# APRDL_2016_4L.net
KiCad netlist of a schematic drawn in EAGLE
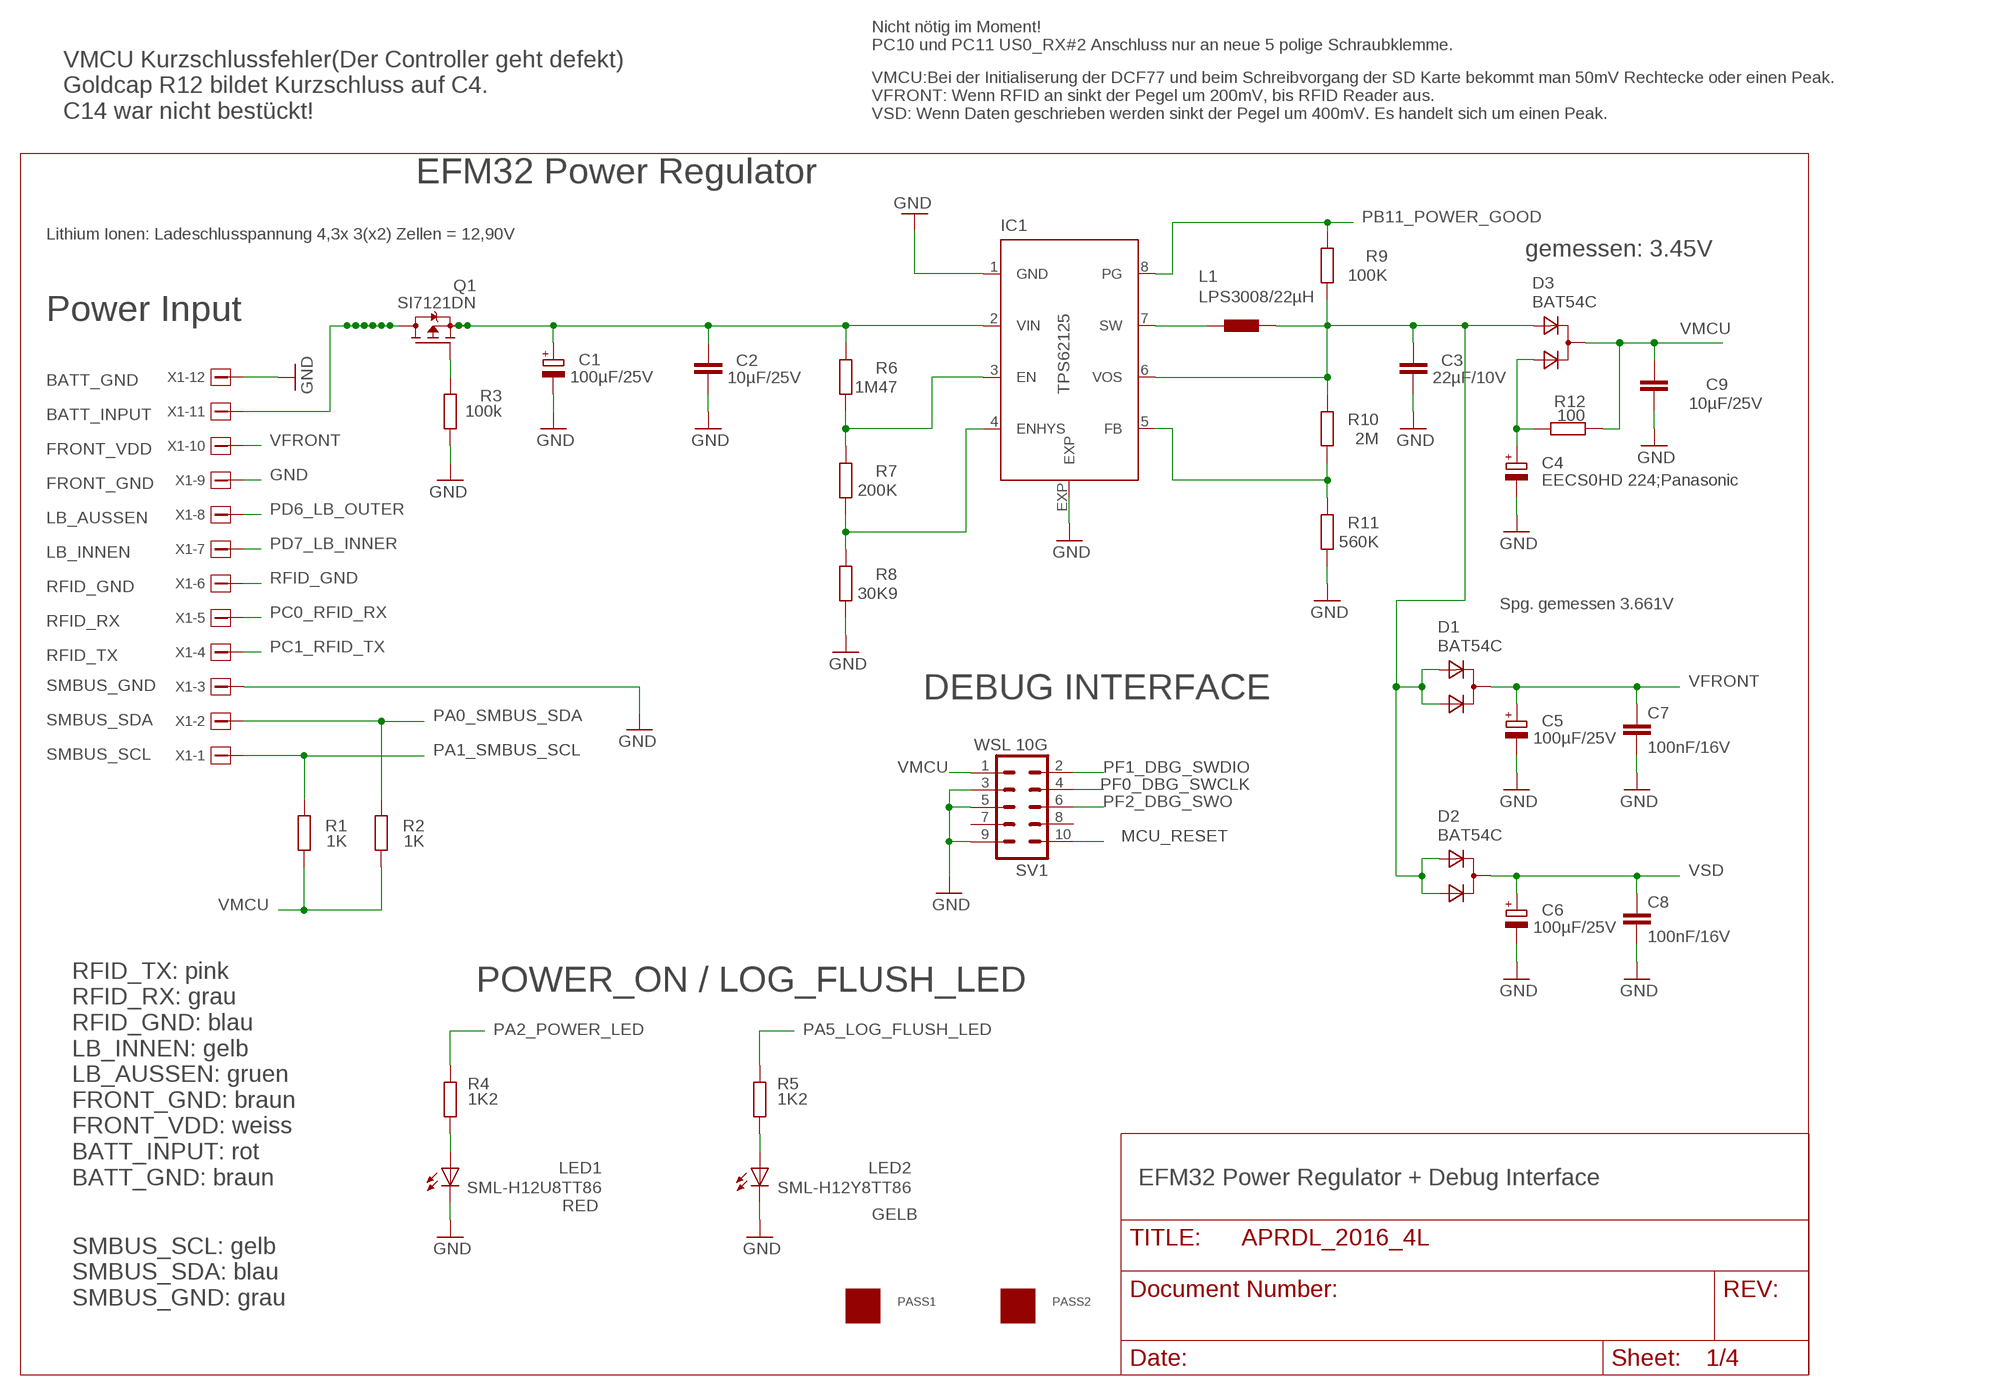
[diagram p0: schematic, sheet 1]
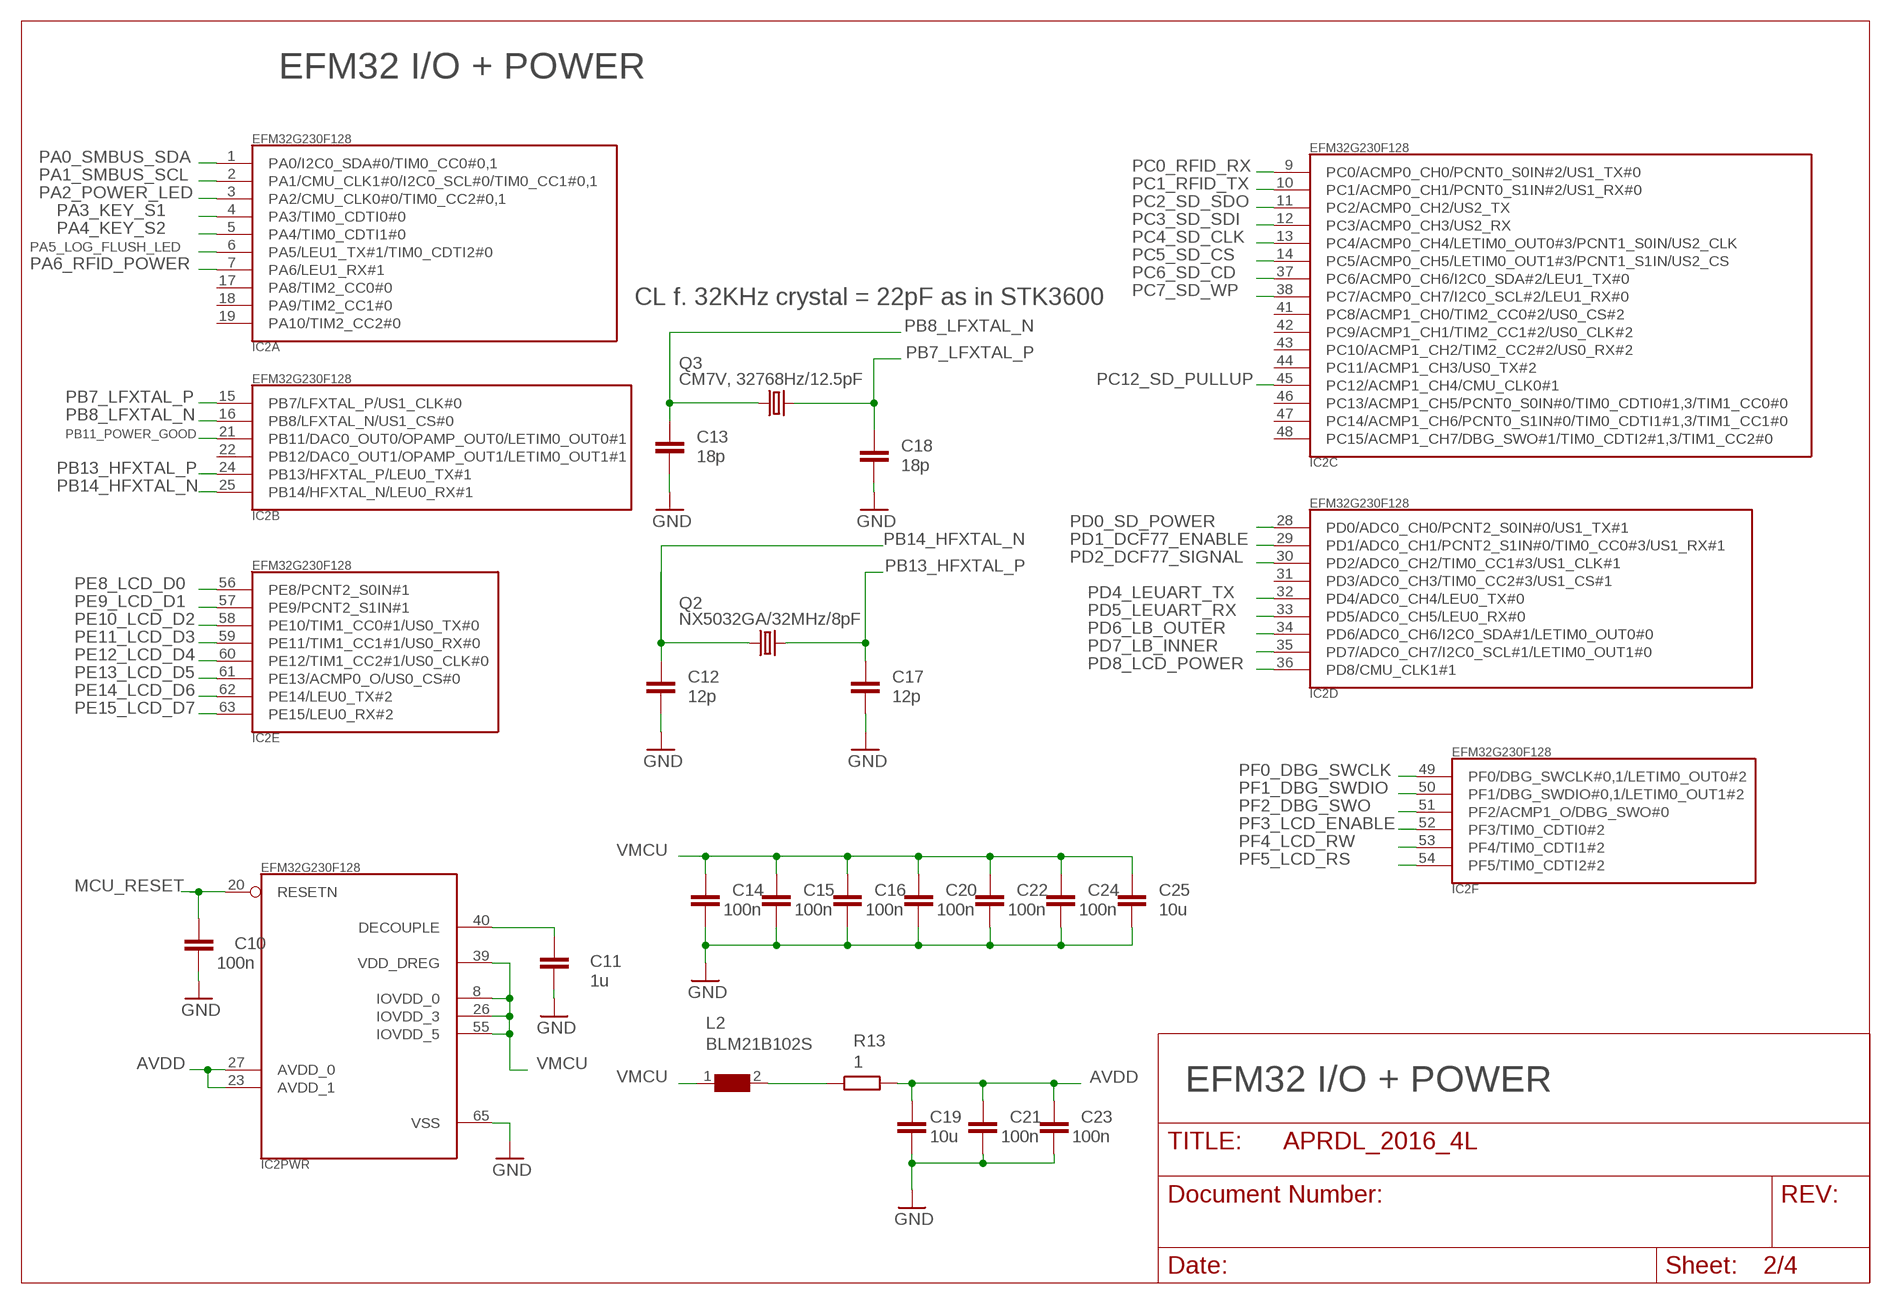
[diagram p1: schematic, sheet 2]
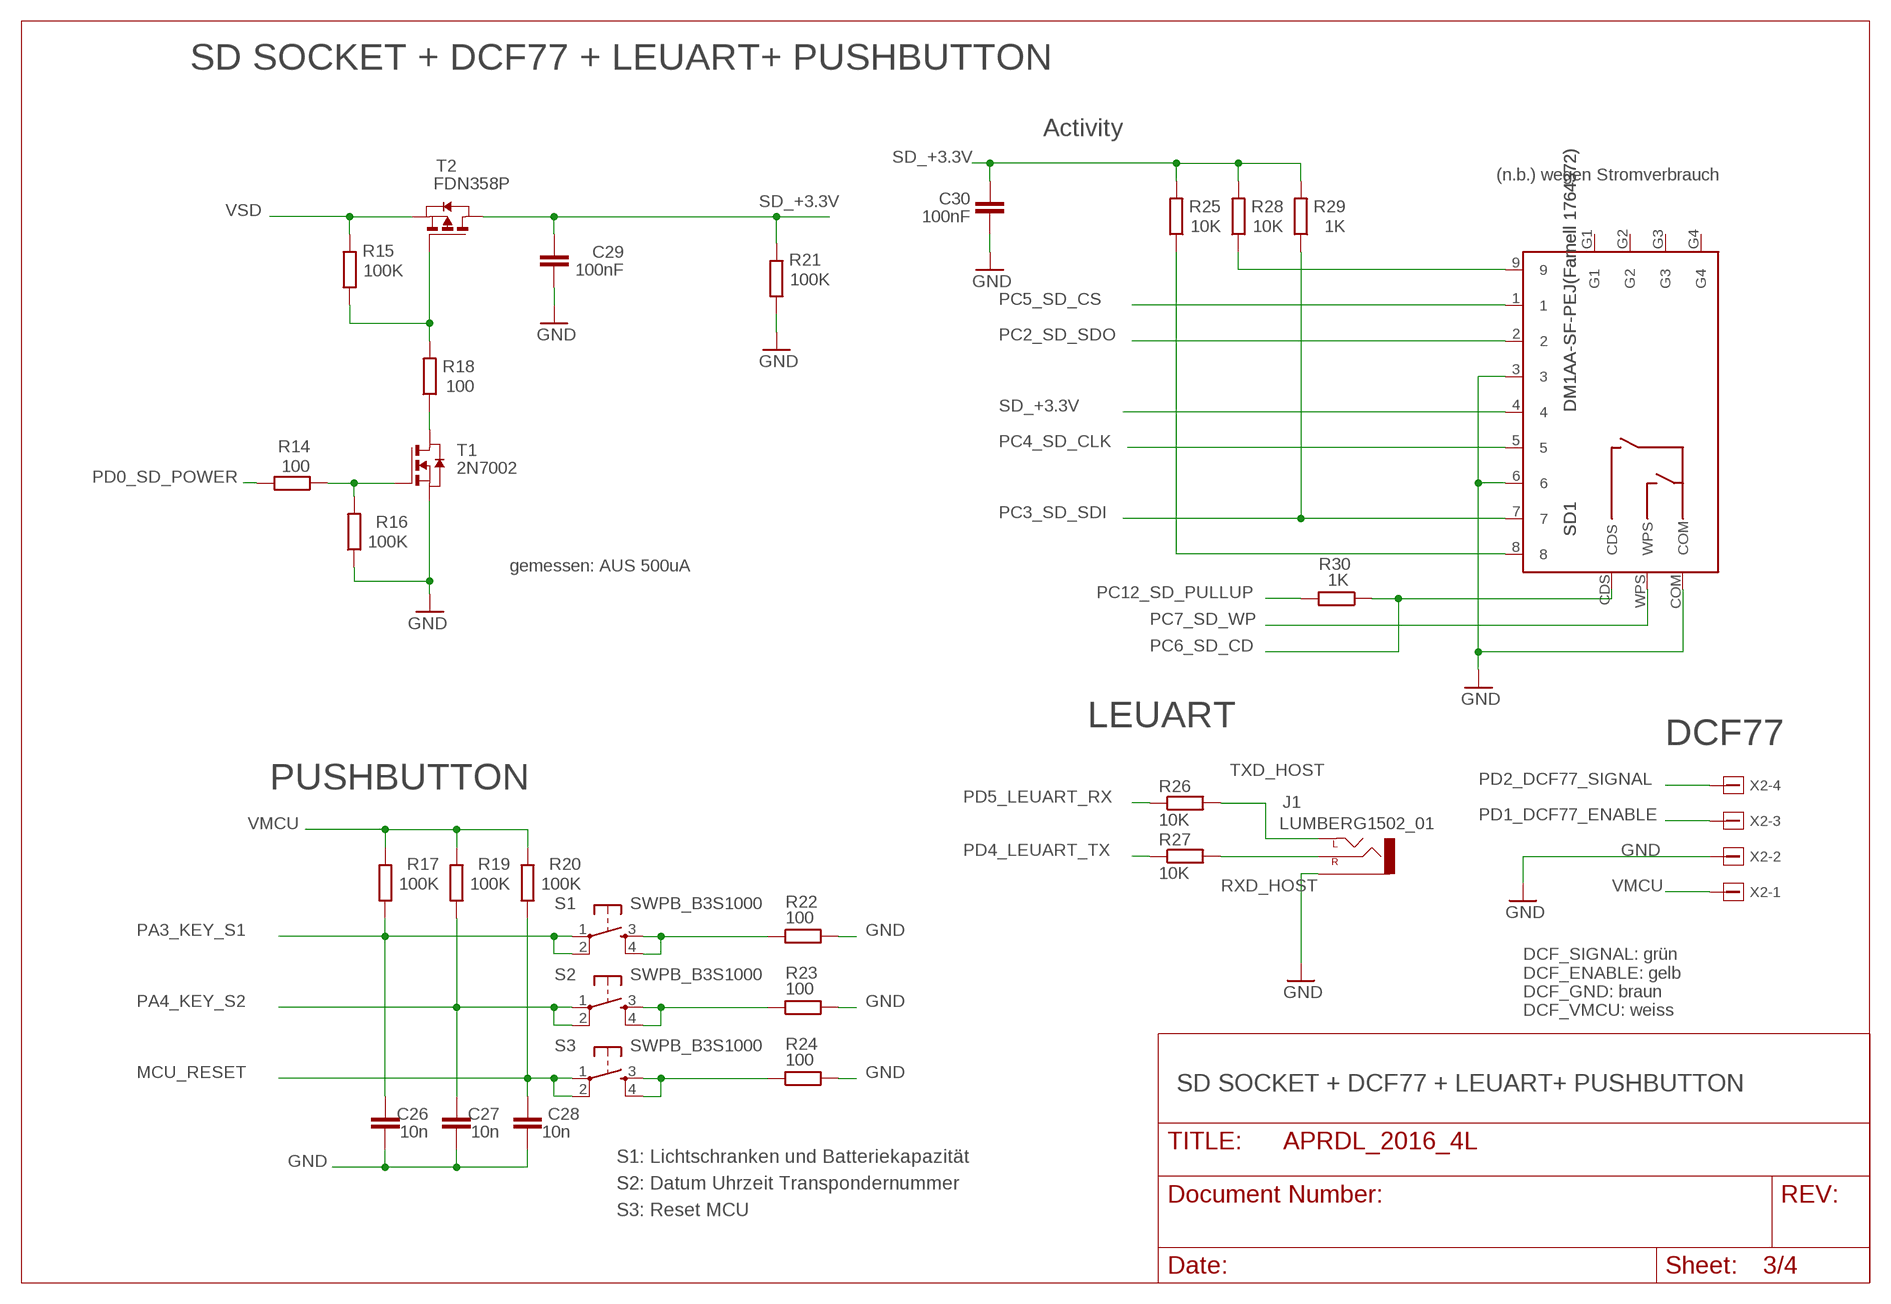
[diagram p2: schematic, sheet 3]
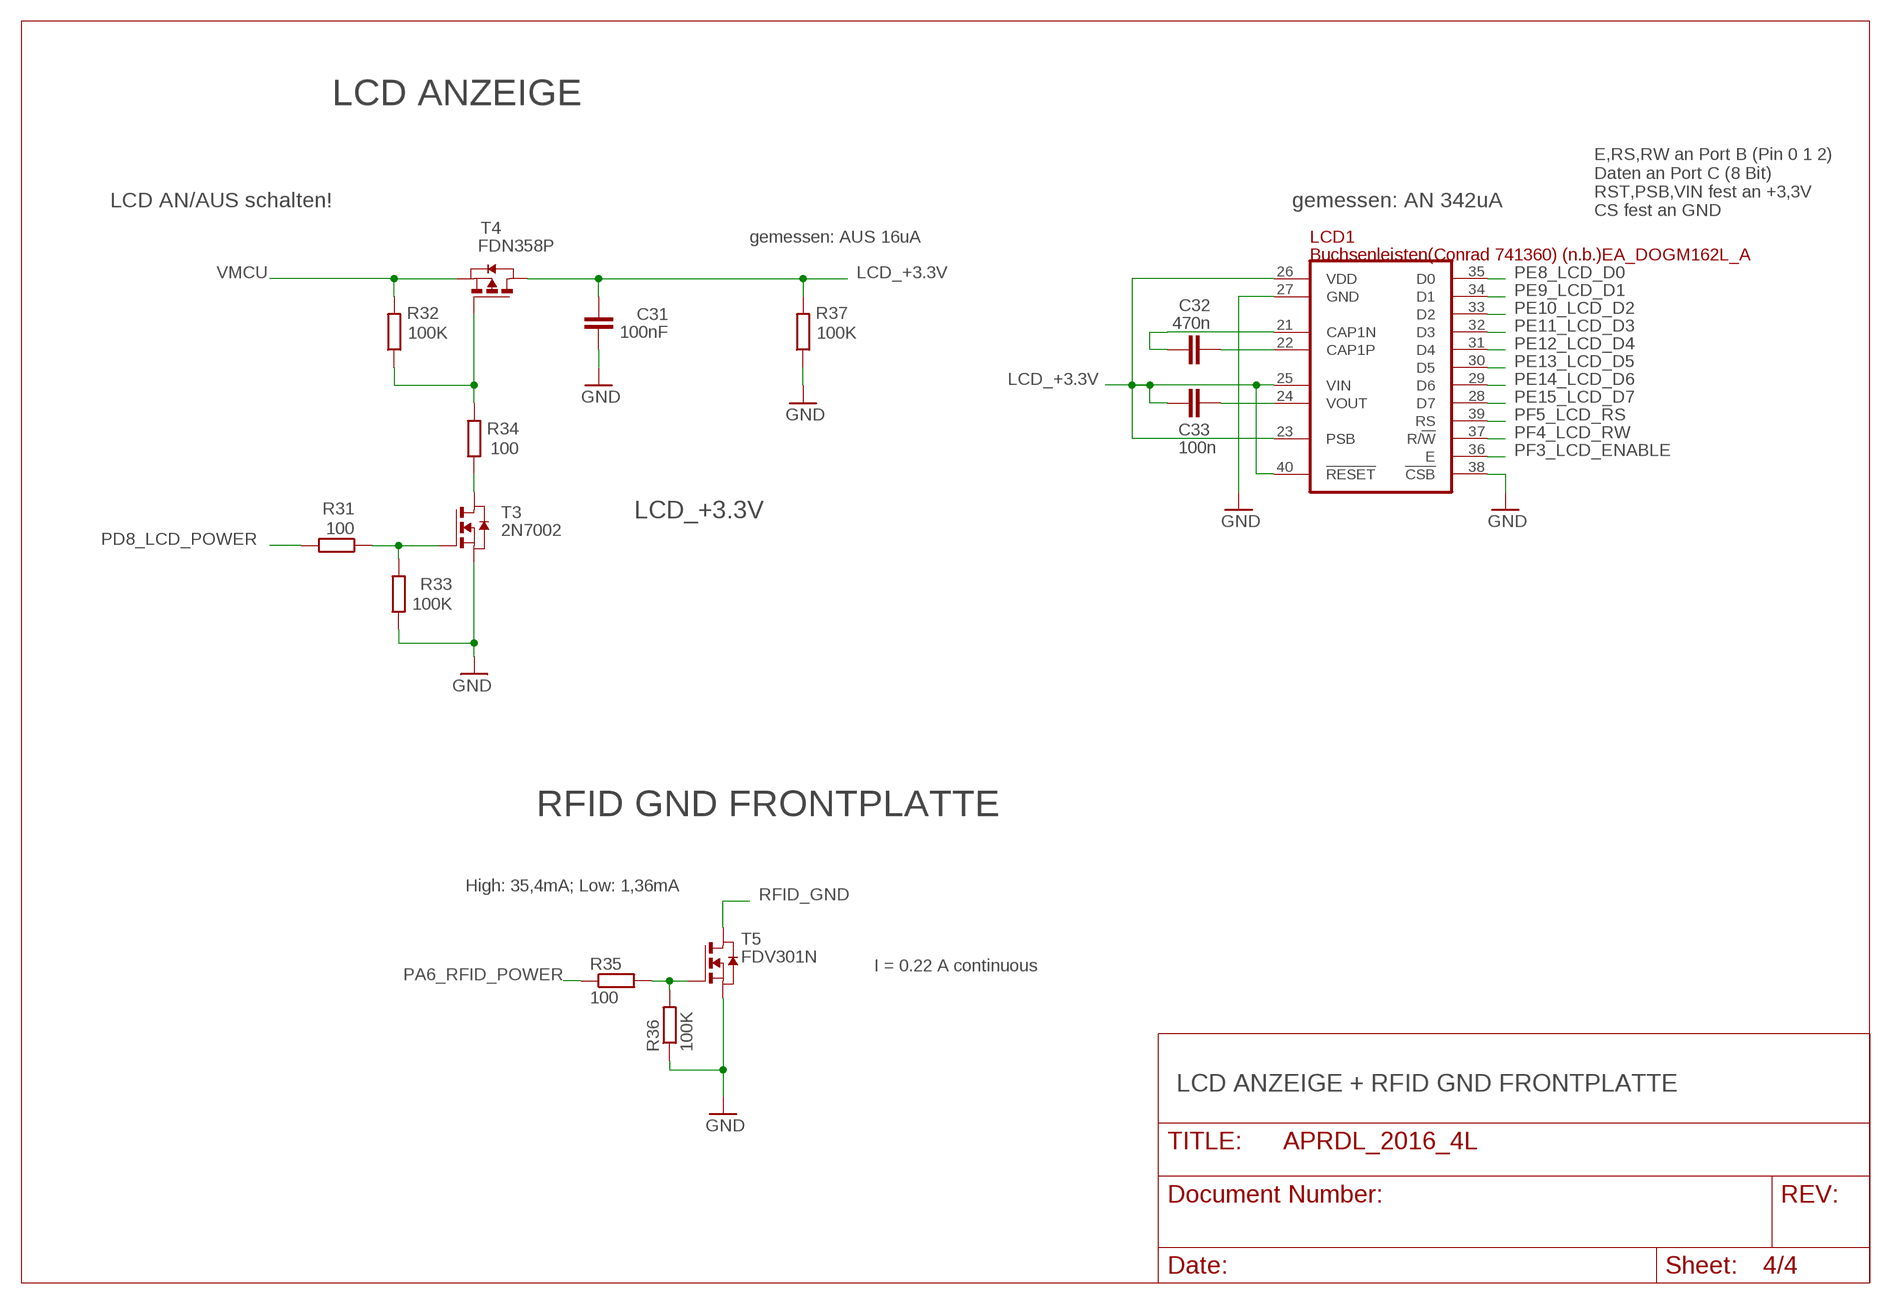
[diagram p3: schematic, sheet 4]

(export (version "E")
  (design (tool "Eeschema 10.0.6"))
  (components
    (comp (ref "C10")
      (value "100n")
      (footprint "eagle-import:C0805")
      (libsource (lib "eagle-import") (part "C-EUC0805"))
    )
    (comp (ref "C11")
      (value "1u")
      (footprint "eagle-import:C0805")
      (libsource (lib "eagle-import") (part "C-EUC0805"))
    )
    (comp (ref "C12")
      (value "12p")
      (footprint "eagle-import:C0805")
      (libsource (lib "eagle-import") (part "C-EUC0805"))
    )
    (comp (ref "C13")
      (value "18p")
      (footprint "eagle-import:C0805")
      (libsource (lib "eagle-import") (part "C-EUC0805"))
    )
    (comp (ref "C14")
      (value "100n")
      (footprint "eagle-import:C0805")
      (libsource (lib "eagle-import") (part "C-EUC0805"))
    )
    (comp (ref "C15")
      (value "100n")
      (footprint "eagle-import:C0805")
      (libsource (lib "eagle-import") (part "C-EUC0805"))
    )
    (comp (ref "C16")
      (value "100n")
      (footprint "eagle-import:C0805")
      (libsource (lib "eagle-import") (part "C-EUC0805"))
    )
    (comp (ref "C17")
      (value "12p")
      (footprint "eagle-import:C0805")
      (libsource (lib "eagle-import") (part "C-EUC0805"))
    )
    (comp (ref "C18")
      (value "18p")
      (footprint "eagle-import:C0805")
      (libsource (lib "eagle-import") (part "C-EUC0805"))
    )
    (comp (ref "C19")
      (value "10u")
      (footprint "eagle-import:C0805")
      (libsource (lib "eagle-import") (part "C-EUC0805"))
    )
    (comp (ref "C20")
      (value "100n")
      (footprint "eagle-import:C0805")
      (libsource (lib "eagle-import") (part "C-EUC0805"))
    )
    (comp (ref "C21")
      (value "100n")
      (footprint "eagle-import:C0805")
      (libsource (lib "eagle-import") (part "C-EUC0805"))
    )
    (comp (ref "C22")
      (value "100n")
      (footprint "eagle-import:C0805")
      (libsource (lib "eagle-import") (part "C-EUC0805"))
    )
    (comp (ref "C23")
      (value "100n")
      (footprint "eagle-import:C0805")
      (libsource (lib "eagle-import") (part "C-EUC0805"))
    )
    (comp (ref "C24")
      (value "100n")
      (footprint "eagle-import:C0805")
      (libsource (lib "eagle-import") (part "C-EUC0805"))
    )
    (comp (ref "C25")
      (value "10u")
      (footprint "eagle-import:C0805")
      (libsource (lib "eagle-import") (part "C-EUC0805"))
    )
    (comp (ref "IC2")
      (value "EFM32G230F128")
      (footprint "eagle-import:QFN64")
      (libsource (lib "eagle-import") (part "EFM32G230F128"))
    )
    (comp (ref "L2")
      (value "BLM21B102S")
      (footprint "eagle-import:0805")
      (fields (field (name "MPN") "7427920"))
      (libsource (lib "eagle-import") (part "WE-CBF_0805-7427920"))
    )
    (comp (ref "Q2")
      (value "NX5032GA/32MHz/8pF")
      (footprint "eagle-import:CRYSTAL2P5.0X3.2")
      (libsource (lib "eagle-import") (part "CRYSTAL2P5.0X3.2"))
    )
    (comp (ref "Q3")
      (value "CM7V, 32768Hz/12.5pF")
      (footprint "eagle-import:CRYSTAL2P3.2X1.5")
      (libsource (lib "eagle-import") (part "CRYSTAL2P"))
    )
    (comp (ref "R13")
      (value "1")
      (footprint "eagle-import:R0805")
      (libsource (lib "eagle-import") (part "R-EU_R0805"))
    )
    (comp (ref "C31")
      (value "100nF")
      (footprint "eagle-import:C0603")
      (libsource (lib "eagle-import") (part "resistor_C-EUC0603"))
    )
    (comp (ref "C32")
      (value "470n")
      (footprint "eagle-import:C0805")
      (libsource (lib "eagle-import") (part "C-EUC0805"))
    )
    (comp (ref "C33")
      (value "100n")
      (footprint "eagle-import:C1206")
      (libsource (lib "eagle-import") (part "C-EUC1206"))
    )
    (comp (ref "LCD1")
      (value "Buchsenleisten(Conrad 741360) (n.b.)EA_DOGM162L_A")
      (footprint "eagle-import:EA_DOGM")
      (libsource (lib "eagle-import") (part "EA_DOGM162"))
    )
    (comp (ref "R31")
      (value "100")
      (footprint "eagle-import:R0805")
      (libsource (lib "eagle-import") (part "resistor_R-EU_R0805"))
    )
    (comp (ref "R32")
      (value "100K")
      (footprint "eagle-import:R0805")
      (libsource (lib "eagle-import") (part "resistor_R-EU_R0805"))
    )
    (comp (ref "R33")
      (value "100K")
      (footprint "eagle-import:R0805")
      (libsource (lib "eagle-import") (part "resistor_R-EU_R0805"))
    )
    (comp (ref "R34")
      (value "100")
      (footprint "eagle-import:R0805")
      (libsource (lib "eagle-import") (part "resistor_R-EU_R0805"))
    )
    (comp (ref "R35")
      (value "100")
      (footprint "eagle-import:R0805")
      (libsource (lib "eagle-import") (part "R-EU_R0805"))
    )
    (comp (ref "R36")
      (value "100K")
      (footprint "eagle-import:R0805")
      (libsource (lib "eagle-import") (part "R-EU_R0805"))
    )
    (comp (ref "R37")
      (value "100K")
      (footprint "eagle-import:R0805")
      (libsource (lib "eagle-import") (part "resistor_R-EU_R0805"))
    )
    (comp (ref "T3")
      (value "2N7002")
      (footprint "eagle-import:ZETEX_SOT-23")
      (libsource (lib "eagle-import") (part "ZETEX_NMOSSOT23"))
    )
    (comp (ref "T4")
      (value "FDN358P")
      (footprint "eagle-import:ZETEX_SOT-23")
      (libsource (lib "eagle-import") (part "ZETEX_PMOSSOT23"))
    )
    (comp (ref "T5")
      (value "FDV301N")
      (footprint "eagle-import:SOT-23")
      (fields (field (name "OC_FARNELL") "unknown") (field (name "OC_NEWARK") "unknown"))
      (libsource (lib "eagle-import") (part "NMOSSOT23"))
    )
    (comp (ref "C26")
      (value "10n")
      (footprint "eagle-import:C0603")
      (libsource (lib "eagle-import") (part "resistor_C-EUC0603"))
    )
    (comp (ref "C27")
      (value "10n")
      (footprint "eagle-import:C0603")
      (libsource (lib "eagle-import") (part "resistor_C-EUC0603"))
    )
    (comp (ref "C28")
      (value "10n")
      (footprint "eagle-import:C0603")
      (libsource (lib "eagle-import") (part "resistor_C-EUC0603"))
    )
    (comp (ref "C29")
      (value "100nF")
      (footprint "eagle-import:C0603")
      (libsource (lib "eagle-import") (part "resistor_C-EUC0603"))
    )
    (comp (ref "C30")
      (value "100nF")
      (footprint "eagle-import:C0603")
      (libsource (lib "eagle-import") (part "resistor_C-EUC0603"))
    )
    (comp (ref "J1")
      (value "LUMBERG1502_01")
      (footprint "eagle-import:LUMBERG1502_01")
      (libsource (lib "eagle-import") (part "LUMBERG1502_01"))
    )
    (comp (ref "R14")
      (value "100")
      (footprint "eagle-import:R0805")
      (libsource (lib "eagle-import") (part "resistor_R-EU_R0805"))
    )
    (comp (ref "R15")
      (value "100K")
      (footprint "eagle-import:R0805")
      (libsource (lib "eagle-import") (part "resistor_R-EU_R0805"))
    )
    (comp (ref "R16")
      (value "100K")
      (footprint "eagle-import:R0805")
      (libsource (lib "eagle-import") (part "resistor_R-EU_R0805"))
    )
    (comp (ref "R17")
      (value "100K")
      (footprint "eagle-import:R0805")
      (libsource (lib "eagle-import") (part "resistor_R-EU_R0805"))
    )
    (comp (ref "R18")
      (value "100")
      (footprint "eagle-import:R0805")
      (libsource (lib "eagle-import") (part "resistor_R-EU_R0805"))
    )
    (comp (ref "R19")
      (value "100K")
      (footprint "eagle-import:R0805")
      (libsource (lib "eagle-import") (part "resistor_R-EU_R0805"))
    )
    (comp (ref "R20")
      (value "100K")
      (footprint "eagle-import:R0805")
      (libsource (lib "eagle-import") (part "resistor_R-EU_R0805"))
    )
    (comp (ref "R21")
      (value "100K")
      (footprint "eagle-import:R0805")
      (libsource (lib "eagle-import") (part "resistor_R-EU_R0805"))
    )
    (comp (ref "R22")
      (value "100")
      (footprint "eagle-import:R0805")
      (libsource (lib "eagle-import") (part "resistor_R-EU_R0805"))
    )
    (comp (ref "R23")
      (value "100")
      (footprint "eagle-import:R0805")
      (libsource (lib "eagle-import") (part "resistor_R-EU_R0805"))
    )
    (comp (ref "R24")
      (value "100")
      (footprint "eagle-import:R0805")
      (libsource (lib "eagle-import") (part "resistor_R-EU_R0805"))
    )
    (comp (ref "R25")
      (value "10K")
      (footprint "eagle-import:R0805")
      (libsource (lib "eagle-import") (part "resistor_R-EU_R0805"))
    )
    (comp (ref "R26")
      (value "10K")
      (footprint "eagle-import:R0805")
      (libsource (lib "eagle-import") (part "R-EU_R0805"))
    )
    (comp (ref "R27")
      (value "10K")
      (footprint "eagle-import:R0805")
      (libsource (lib "eagle-import") (part "R-EU_R0805"))
    )
    (comp (ref "R28")
      (value "10K")
      (footprint "eagle-import:R0805")
      (libsource (lib "eagle-import") (part "resistor_R-EU_R0805"))
    )
    (comp (ref "R29")
      (value "1K")
      (footprint "eagle-import:R0805")
      (libsource (lib "eagle-import") (part "resistor_R-EU_R0805"))
    )
    (comp (ref "R30")
      (value "1K")
      (footprint "eagle-import:R0805")
      (libsource (lib "eagle-import") (part "resistor_R-EU_R0805"))
    )
    (comp (ref "S1")
      (value "SWPB_B3S1000")
      (footprint "eagle-import:DTSM-6")
      (libsource (lib "eagle-import") (part "DTSM-6"))
    )
    (comp (ref "S2")
      (value "SWPB_B3S1000")
      (footprint "eagle-import:DTSM-6")
      (libsource (lib "eagle-import") (part "DTSM-6"))
    )
    (comp (ref "S3")
      (value "SWPB_B3S1000")
      (footprint "eagle-import:DTSM-6")
      (libsource (lib "eagle-import") (part "DTSM-6"))
    )
    (comp (ref "SD1")
      (value "DM1AA-SF-PEJ(Farnell 1764372)")
      (footprint "eagle-import:DM1AA-SF-PEJ")
      (libsource (lib "eagle-import") (part "DM1AA-SF-PEJ"))
    )
    (comp (ref "T1")
      (value "2N7002")
      (footprint "eagle-import:ZETEX_SOT-23")
      (libsource (lib "eagle-import") (part "ZETEX_NMOSSOT23"))
    )
    (comp (ref "T2")
      (value "FDN358P")
      (footprint "eagle-import:ZETEX_SOT-23")
      (libsource (lib "eagle-import") (part "ZETEX_PMOSSOT23"))
    )
    (comp (ref "X2")
      (value "1803442")
      (footprint "eagle-import:1803442")
      (libsource (lib "eagle-import") (part "1803442"))
    )
    (comp (ref "C1")
      (value "100µF/25V")
      (footprint "eagle-import:PANASONIC_E")
      (libsource (lib "eagle-import") (part "CPOL-EUE"))
    )
    (comp (ref "C2")
      (value "10µF/25V")
      (footprint "eagle-import:C1206")
      (libsource (lib "eagle-import") (part "C-EUC1206"))
    )
    (comp (ref "C3")
      (value "22µF/10V")
      (footprint "eagle-import:C1206")
      (libsource (lib "eagle-import") (part "C-EUC1206"))
    )
    (comp (ref "C4")
      (value "EECS0HD 224;Panasonic")
      (footprint "eagle-import:GOLDCAPSPK-V")
      (libsource (lib "eagle-import") (part "GOLDCAPSPK-V"))
    )
    (comp (ref "C5")
      (value "100µF/25V")
      (footprint "eagle-import:PANASONIC_E")
      (libsource (lib "eagle-import") (part "CPOL-EUE"))
    )
    (comp (ref "C6")
      (value "100µF/25V")
      (footprint "eagle-import:PANASONIC_E")
      (libsource (lib "eagle-import") (part "CPOL-EUE"))
    )
    (comp (ref "C7")
      (value "100nF/16V")
      (footprint "eagle-import:C0805")
      (libsource (lib "eagle-import") (part "C-EUC0805"))
    )
    (comp (ref "C8")
      (value "100nF/16V")
      (footprint "eagle-import:C0805")
      (libsource (lib "eagle-import") (part "C-EUC0805"))
    )
    (comp (ref "C9")
      (value "10µF/25V")
      (footprint "eagle-import:C1206")
      (libsource (lib "eagle-import") (part "C-EUC1206"))
    )
    (comp (ref "D1")
      (value "BAT54C")
      (footprint "eagle-import:SOT-23@1")
      (libsource (lib "eagle-import") (part "D2A_SOT23"))
    )
    (comp (ref "D2")
      (value "BAT54C")
      (footprint "eagle-import:SOT-23@1")
      (libsource (lib "eagle-import") (part "D2A_SOT23"))
    )
    (comp (ref "D3")
      (value "BAT54C")
      (footprint "eagle-import:SOT-23@1")
      (libsource (lib "eagle-import") (part "D2A_SOT23"))
    )
    (comp (ref "IC1")
      (value "TPS62125")
      (footprint "eagle-import:DSG_PWSO-N8_EXP")
      (libsource (lib "eagle-import") (part "TPS62125"))
    )
    (comp (ref "L1")
      (value "LPS3008/22µH")
      (footprint "eagle-import:LPS3008")
      (libsource (lib "eagle-import") (part "LPS3008"))
    )
    (comp (ref "LED1")
      (value "SML-H12U8TT86")
      (footprint "eagle-import:CHIPLED_0805")
      (libsource (lib "eagle-import") (part "LEDCHIPLED_0805"))
    )
    (comp (ref "LED2")
      (value "SML-H12Y8TT86")
      (footprint "eagle-import:CHIPLED_0805")
      (libsource (lib "eagle-import") (part "LEDCHIPLED_0805"))
    )
    (comp (ref "PASS1")
      (value "ROUND_1MM1.5")
      (footprint "eagle-import:ROUND2_1.5MM")
      (libsource (lib "eagle-import") (part "ROUND_1MM1.5"))
    )
    (comp (ref "PASS2")
      (value "ROUND_1MM1.5")
      (footprint "eagle-import:ROUND2_1.5MM")
      (libsource (lib "eagle-import") (part "ROUND_1MM1.5"))
    )
    (comp (ref "Q1")
      (value "SI7121DN")
      (footprint "eagle-import:TRANSISTOR-FET_1212-8S")
      (libsource (lib "eagle-import") (part "TRANSISTOR-FET_SI7113DN"))
    )
    (comp (ref "R1")
      (value "1K")
      (footprint "eagle-import:R0805")
      (libsource (lib "eagle-import") (part "resistor_R-EU_R0805"))
    )
    (comp (ref "R2")
      (value "1K")
      (footprint "eagle-import:R0805")
      (libsource (lib "eagle-import") (part "resistor_R-EU_R0805"))
    )
    (comp (ref "R3")
      (value "100k")
      (footprint "eagle-import:R0805")
      (libsource (lib "eagle-import") (part "resistor_R-EU_R0805"))
    )
    (comp (ref "R4")
      (value "1K2")
      (footprint "eagle-import:R0805")
      (libsource (lib "eagle-import") (part "resistor_R-EU_R0805"))
    )
    (comp (ref "R5")
      (value "1K2")
      (footprint "eagle-import:R0805")
      (libsource (lib "eagle-import") (part "resistor_R-EU_R0805"))
    )
    (comp (ref "R6")
      (value "1M47")
      (footprint "eagle-import:R0805")
      (libsource (lib "eagle-import") (part "R-EU_R0805"))
    )
    (comp (ref "R7")
      (value "200K")
      (footprint "eagle-import:R0805")
      (libsource (lib "eagle-import") (part "R-EU_R0805"))
    )
    (comp (ref "R8")
      (value "30K9")
      (footprint "eagle-import:R0805")
      (libsource (lib "eagle-import") (part "R-EU_R0805"))
    )
    (comp (ref "R9")
      (value "100K")
      (footprint "eagle-import:R0805")
      (libsource (lib "eagle-import") (part "R-EU_R0805"))
    )
    (comp (ref "R10")
      (value "2M")
      (footprint "eagle-import:R0805")
      (libsource (lib "eagle-import") (part "R-EU_R0805"))
    )
    (comp (ref "R11")
      (value "560K")
      (footprint "eagle-import:R0805")
      (libsource (lib "eagle-import") (part "R-EU_R0805"))
    )
    (comp (ref "R12")
      (value "100")
      (footprint "eagle-import:R0805")
      (libsource (lib "eagle-import") (part "R-EU_R0805"))
    )
    (comp (ref "SV1")
      (value "WSL 10G")
      (footprint "eagle-import:ML10")
      (libsource (lib "eagle-import") (part "ML10"))
    )
    (comp (ref "X1")
      (value "1803523")
      (footprint "eagle-import:1803523")
      (libsource (lib "eagle-import") (part "1803523"))
    )
  )
  (nets
    (net (code "1") (name "AVDD") (class "Default")
      (node (ref "C19") (pin "2") (pinfunction "2_2") (pintype "passive"))
      (node (ref "C21") (pin "2") (pinfunction "2_2") (pintype "passive"))
      (node (ref "C23") (pin "2") (pinfunction "2_2") (pintype "passive"))
      (node (ref "IC2") (pin "23") (pinfunction "AVDD_1_23") (pintype "power_in"))
      (node (ref "IC2") (pin "27") (pinfunction "AVDD_0_27") (pintype "power_in"))
      (node (ref "R13") (pin "2") (pinfunction "2_2") (pintype "passive"))
    )
    (net (code "2") (name "GND") (class "Default")
      (node (ref "C1") (pin "-") (pinfunction "-_-") (pintype "passive"))
      (node (ref "C10") (pin "1") (pinfunction "1_1") (pintype "passive"))
      (node (ref "C11") (pin "1") (pinfunction "1_1") (pintype "passive"))
      (node (ref "C12") (pin "1") (pinfunction "1_1") (pintype "passive"))
      (node (ref "C13") (pin "1") (pinfunction "1_1") (pintype "passive"))
      (node (ref "C14") (pin "1") (pinfunction "1_1") (pintype "passive"))
      (node (ref "C15") (pin "1") (pinfunction "1_1") (pintype "passive"))
      (node (ref "C16") (pin "1") (pinfunction "1_1") (pintype "passive"))
      (node (ref "C17") (pin "1") (pinfunction "1_1") (pintype "passive"))
      (node (ref "C18") (pin "1") (pinfunction "1_1") (pintype "passive"))
      (node (ref "C19") (pin "1") (pinfunction "1_1") (pintype "passive"))
      (node (ref "C2") (pin "2") (pinfunction "2_2") (pintype "passive"))
      (node (ref "C20") (pin "1") (pinfunction "1_1") (pintype "passive"))
      (node (ref "C21") (pin "1") (pinfunction "1_1") (pintype "passive"))
      (node (ref "C22") (pin "1") (pinfunction "1_1") (pintype "passive"))
      (node (ref "C23") (pin "1") (pinfunction "1_1") (pintype "passive"))
      (node (ref "C24") (pin "1") (pinfunction "1_1") (pintype "passive"))
      (node (ref "C25") (pin "1") (pinfunction "1_1") (pintype "passive"))
      (node (ref "C26") (pin "1") (pinfunction "1_1") (pintype "passive"))
      (node (ref "C27") (pin "1") (pinfunction "1_1") (pintype "passive"))
      (node (ref "C28") (pin "1") (pinfunction "1_1") (pintype "passive"))
      (node (ref "C29") (pin "2") (pinfunction "2_2") (pintype "passive"))
      (node (ref "C3") (pin "2") (pinfunction "2_2") (pintype "passive"))
      (node (ref "C30") (pin "2") (pinfunction "2_2") (pintype "passive"))
      (node (ref "C31") (pin "2") (pinfunction "2_2") (pintype "passive"))
      (node (ref "C4") (pin "-") (pinfunction "-_-") (pintype "passive"))
      (node (ref "C5") (pin "-") (pinfunction "-_-") (pintype "passive"))
      (node (ref "C6") (pin "-") (pinfunction "-_-") (pintype "passive"))
      (node (ref "C7") (pin "2") (pinfunction "2_2") (pintype "passive"))
      (node (ref "C8") (pin "2") (pinfunction "2_2") (pintype "passive"))
      (node (ref "C9") (pin "1") (pinfunction "1_1") (pintype "passive"))
      (node (ref "IC1") (pin "1") (pinfunction "GND_1") (pintype "passive"))
      (node (ref "IC1") (pin "EXP") (pinfunction "EXP_EXP") (pintype "passive"))
      (node (ref "IC2") (pin "65") (pinfunction "VSS_65") (pintype "power_in"))
      (node (ref "J1") (pin "P$1") (pinfunction "1-SLEEVE_P$1") (pintype "bidirectional"))
      (node (ref "LCD1") (pin "27") (pinfunction "GND_27") (pintype "power_in"))
      (node (ref "LCD1") (pin "38") (pinfunction "~{CSB}_38") (pintype "input"))
      (node (ref "LED1") (pin "C") (pinfunction "C_C") (pintype "passive"))
      (node (ref "LED2") (pin "C") (pinfunction "C_C") (pintype "passive"))
      (node (ref "R11") (pin "1") (pinfunction "1_1") (pintype "passive"))
      (node (ref "R16") (pin "1") (pinfunction "1_1") (pintype "passive"))
      (node (ref "R21") (pin "1") (pinfunction "1_1") (pintype "passive"))
      (node (ref "R22") (pin "2") (pinfunction "2_2") (pintype "passive"))
      (node (ref "R23") (pin "2") (pinfunction "2_2") (pintype "passive"))
      (node (ref "R24") (pin "2") (pinfunction "2_2") (pintype "passive"))
      (node (ref "R3") (pin "1") (pinfunction "1_1") (pintype "passive"))
      (node (ref "R33") (pin "1") (pinfunction "1_1") (pintype "passive"))
      (node (ref "R36") (pin "1") (pinfunction "1_1") (pintype "passive"))
      (node (ref "R37") (pin "1") (pinfunction "1_1") (pintype "passive"))
      (node (ref "R8") (pin "1") (pinfunction "1_1") (pintype "passive"))
      (node (ref "SD1") (pin "3") (pinfunction "3_3") (pintype "bidirectional"))
      (node (ref "SD1") (pin "6") (pinfunction "6_6") (pintype "bidirectional"))
      (node (ref "SD1") (pin "COM") (pinfunction "COM_COM") (pintype "passive"))
      (node (ref "SV1") (pin "3") (pinfunction "3_3") (pintype "passive"))
      (node (ref "SV1") (pin "5") (pinfunction "5_5") (pintype "passive"))
      (node (ref "SV1") (pin "9") (pinfunction "9_9") (pintype "passive"))
      (node (ref "T1") (pin "2") (pinfunction "S_2") (pintype "passive"))
      (node (ref "T3") (pin "2") (pinfunction "S_2") (pintype "passive"))
      (node (ref "T5") (pin "2") (pinfunction "S_2") (pintype "passive"))
      (node (ref "X1") (pin "12") (pinfunction "1_12") (pintype "passive"))
      (node (ref "X1") (pin "3") (pinfunction "1_3") (pintype "passive"))
      (node (ref "X1") (pin "9") (pinfunction "1_9") (pintype "passive"))
      (node (ref "X2") (pin "2") (pinfunction "1_2") (pintype "passive"))
    )
    (net (code "3") (name "LCD_+3.3V") (class "Default")
      (node (ref "C31") (pin "1") (pinfunction "1_1") (pintype "passive"))
      (node (ref "C33") (pin "2") (pinfunction "2_2") (pintype "passive"))
      (node (ref "LCD1") (pin "23") (pinfunction "PSB_23") (pintype "input"))
      (node (ref "LCD1") (pin "25") (pinfunction "VIN_25") (pintype "passive"))
      (node (ref "LCD1") (pin "26") (pinfunction "VDD_26") (pintype "power_in"))
      (node (ref "LCD1") (pin "40") (pinfunction "~{RESET}_40") (pintype "input"))
      (node (ref "R37") (pin "2") (pinfunction "2_2") (pintype "passive"))
      (node (ref "T4") (pin "1") (pinfunction "D_1") (pintype "passive"))
    )
    (net (code "4") (name "MCU_RESET") (class "Default")
      (node (ref "C10") (pin "2") (pinfunction "2_2") (pintype "passive"))
      (node (ref "C28") (pin "2") (pinfunction "2_2") (pintype "passive"))
      (node (ref "IC2") (pin "20") (pinfunction "RESETN_20") (pintype "passive"))
      (node (ref "R20") (pin "1") (pinfunction "1_1") (pintype "passive"))
      (node (ref "S3") (pin "1") (pinfunction "1_1") (pintype "passive"))
      (node (ref "S3") (pin "2") (pinfunction "2_2") (pintype "passive"))
      (node (ref "SV1") (pin "10") (pinfunction "10_10") (pintype "passive"))
    )
    (net (code "5") (name "Net-(D1-A1)") (class "Default")
      (node (ref "C3") (pin "1") (pinfunction "1_1") (pintype "passive"))
      (node (ref "D1") (pin "2") (pinfunction "A1_2") (pintype "passive"))
      (node (ref "D1") (pin "3") (pinfunction "A2_3") (pintype "passive"))
      (node (ref "D2") (pin "2") (pinfunction "A1_2") (pintype "passive"))
      (node (ref "D2") (pin "3") (pinfunction "A2_3") (pintype "passive"))
      (node (ref "D3") (pin "3") (pinfunction "A2_3") (pintype "passive"))
      (node (ref "IC1") (pin "6") (pinfunction "VOS_6") (pintype "input"))
      (node (ref "L1") (pin "2") (pinfunction "2_2") (pintype "passive"))
      (node (ref "R10") (pin "2") (pinfunction "2_2") (pintype "passive"))
      (node (ref "R9") (pin "1") (pinfunction "1_1") (pintype "passive"))
    )
    (net (code "6") (name "Net-(D3-A1)") (class "Default")
      (node (ref "C4") (pin "+") (pinfunction "+_+") (pintype "passive"))
      (node (ref "D3") (pin "2") (pinfunction "A1_2") (pintype "passive"))
      (node (ref "R12") (pin "2") (pinfunction "2_2") (pintype "passive"))
    )
    (net (code "7") (name "Net-(IC1-EN)") (class "Default")
      (node (ref "IC1") (pin "3") (pinfunction "EN_3") (pintype "input"))
      (node (ref "R6") (pin "1") (pinfunction "1_1") (pintype "passive"))
      (node (ref "R7") (pin "2") (pinfunction "2_2") (pintype "passive"))
    )
    (net (code "8") (name "Net-(IC1-ENHYS)") (class "Default")
      (node (ref "IC1") (pin "4") (pinfunction "ENHYS_4") (pintype "output"))
      (node (ref "R7") (pin "1") (pinfunction "1_1") (pintype "passive"))
      (node (ref "R8") (pin "2") (pinfunction "2_2") (pintype "passive"))
    )
    (net (code "9") (name "Net-(IC1-FB)") (class "Default")
      (node (ref "IC1") (pin "5") (pinfunction "FB_5") (pintype "input"))
      (node (ref "R10") (pin "1") (pinfunction "1_1") (pintype "passive"))
      (node (ref "R11") (pin "2") (pinfunction "2_2") (pintype "passive"))
    )
    (net (code "10") (name "Net-(IC1-SW)") (class "Default")
      (node (ref "IC1") (pin "7") (pinfunction "SW_7") (pintype "output"))
      (node (ref "L1") (pin "1") (pinfunction "1_1") (pintype "passive"))
    )
    (net (code "11") (name "Net-(IC1-VIN)") (class "Default")
      (node (ref "C1") (pin "+") (pinfunction "+_+") (pintype "passive"))
      (node (ref "C2") (pin "1") (pinfunction "1_1") (pintype "passive"))
      (node (ref "IC1") (pin "2") (pinfunction "VIN_2") (pintype "passive"))
      (node (ref "Q1") (pin "1") (pinfunction "S_1") (pintype "passive"))
      (node (ref "Q1") (pin "2") (pinfunction "S_2") (pintype "passive"))
      (node (ref "Q1") (pin "3") (pinfunction "S_3") (pintype "passive"))
      (node (ref "R6") (pin "2") (pinfunction "2_2") (pintype "passive"))
    )
    (net (code "12") (name "Net-(IC2G-DECOUPLE)") (class "Default")
      (node (ref "C11") (pin "2") (pinfunction "2_2") (pintype "passive"))
      (node (ref "IC2") (pin "40") (pinfunction "DECOUPLE_40") (pintype "power_in"))
    )
    (net (code "13") (name "Net-(L2-Pad2)") (class "Default")
      (node (ref "L2") (pin "2") (pinfunction "2_2") (pintype "passive"))
      (node (ref "R13") (pin "1") (pinfunction "1_1") (pintype "passive"))
    )
    (net (code "14") (name "Net-(LCD1-CAP1N)") (class "Default")
      (node (ref "C32") (pin "1") (pinfunction "1_1") (pintype "passive"))
      (node (ref "LCD1") (pin "21") (pinfunction "CAP1N_21") (pintype "passive"))
    )
    (net (code "15") (name "Net-(LCD1-CAP1P)") (class "Default")
      (node (ref "C32") (pin "2") (pinfunction "2_2") (pintype "passive"))
      (node (ref "LCD1") (pin "22") (pinfunction "CAP1P_22") (pintype "passive"))
    )
    (net (code "16") (name "Net-(LCD1-VOUT)") (class "Default")
      (node (ref "C33") (pin "1") (pinfunction "1_1") (pintype "passive"))
      (node (ref "LCD1") (pin "24") (pinfunction "VOUT_24") (pintype "passive"))
    )
    (net (code "17") (name "Net-(LED1-PadA)") (class "Default")
      (node (ref "LED1") (pin "A") (pinfunction "A_A") (pintype "passive"))
      (node (ref "R4") (pin "2") (pinfunction "2_2") (pintype "passive"))
    )
    (net (code "18") (name "Net-(LED2-PadA)") (class "Default")
      (node (ref "LED2") (pin "A") (pinfunction "A_A") (pintype "passive"))
      (node (ref "R5") (pin "2") (pinfunction "2_2") (pintype "passive"))
    )
    (net (code "19") (name "Net-(Q1-G)") (class "Default")
      (node (ref "Q1") (pin "4") (pinfunction "G_4") (pintype "passive"))
      (node (ref "R3") (pin "2") (pinfunction "2_2") (pintype "passive"))
    )
    (net (code "20") (name "Net-(R22-Pad1)") (class "Default")
      (node (ref "R22") (pin "1") (pinfunction "1_1") (pintype "passive"))
      (node (ref "S1") (pin "3") (pinfunction "3_3") (pintype "passive"))
      (node (ref "S1") (pin "4") (pinfunction "4_4") (pintype "passive"))
    )
    (net (code "21") (name "Net-(R23-Pad1)") (class "Default")
      (node (ref "R23") (pin "1") (pinfunction "1_1") (pintype "passive"))
      (node (ref "S2") (pin "3") (pinfunction "3_3") (pintype "passive"))
      (node (ref "S2") (pin "4") (pinfunction "4_4") (pintype "passive"))
    )
    (net (code "22") (name "Net-(R24-Pad1)") (class "Default")
      (node (ref "R24") (pin "1") (pinfunction "1_1") (pintype "passive"))
      (node (ref "S3") (pin "3") (pinfunction "3_3") (pintype "passive"))
      (node (ref "S3") (pin "4") (pinfunction "4_4") (pintype "passive"))
    )
    (net (code "23") (name "Net-(R25-Pad1)") (class "Default")
      (node (ref "R25") (pin "1") (pinfunction "1_1") (pintype "passive"))
      (node (ref "SD1") (pin "8") (pinfunction "8_8") (pintype "bidirectional"))
    )
    (net (code "24") (name "Net-(R28-Pad1)") (class "Default")
      (node (ref "R28") (pin "1") (pinfunction "1_1") (pintype "passive"))
      (node (ref "SD1") (pin "9") (pinfunction "9_9") (pintype "bidirectional"))
    )
    (net (code "25") (name "Net-(T1-D)") (class "Default")
      (node (ref "R18") (pin "1") (pinfunction "1_1") (pintype "passive"))
      (node (ref "T1") (pin "1") (pinfunction "D_1") (pintype "passive"))
    )
    (net (code "26") (name "Net-(T1-G)") (class "Default")
      (node (ref "R14") (pin "1") (pinfunction "1_1") (pintype "passive"))
      (node (ref "R16") (pin "2") (pinfunction "2_2") (pintype "passive"))
      (node (ref "T1") (pin "3") (pinfunction "G_3") (pintype "passive"))
    )
    (net (code "27") (name "Net-(T2-G)") (class "Default")
      (node (ref "R15") (pin "1") (pinfunction "1_1") (pintype "passive"))
      (node (ref "R18") (pin "2") (pinfunction "2_2") (pintype "passive"))
      (node (ref "T2") (pin "3") (pinfunction "G_3") (pintype "passive"))
    )
    (net (code "28") (name "Net-(T3-D)") (class "Default")
      (node (ref "R34") (pin "1") (pinfunction "1_1") (pintype "passive"))
      (node (ref "T3") (pin "1") (pinfunction "D_1") (pintype "passive"))
    )
    (net (code "29") (name "Net-(T3-G)") (class "Default")
      (node (ref "R31") (pin "1") (pinfunction "1_1") (pintype "passive"))
      (node (ref "R33") (pin "2") (pinfunction "2_2") (pintype "passive"))
      (node (ref "T3") (pin "3") (pinfunction "G_3") (pintype "passive"))
    )
    (net (code "30") (name "Net-(T4-G)") (class "Default")
      (node (ref "R32") (pin "1") (pinfunction "1_1") (pintype "passive"))
      (node (ref "R34") (pin "2") (pinfunction "2_2") (pintype "passive"))
      (node (ref "T4") (pin "3") (pinfunction "G_3") (pintype "passive"))
    )
    (net (code "31") (name "Net-(T5-G)") (class "Default")
      (node (ref "R35") (pin "2") (pinfunction "2_2") (pintype "passive"))
      (node (ref "R36") (pin "2") (pinfunction "2_2") (pintype "passive"))
      (node (ref "T5") (pin "3") (pinfunction "G_3") (pintype "passive"))
    )
    (net (code "32") (name "Net-(X1C-1)") (class "Default")
      (node (ref "Q1") (pin "10") (pinfunction "D_10") (pintype "passive"))
      (node (ref "Q1") (pin "11") (pinfunction "D_11") (pintype "passive"))
      (node (ref "Q1") (pin "5") (pinfunction "D_5") (pintype "passive"))
      (node (ref "Q1") (pin "6") (pinfunction "D_6") (pintype "passive"))
      (node (ref "Q1") (pin "7") (pinfunction "D_7") (pintype "passive"))
      (node (ref "Q1") (pin "8") (pinfunction "D_8") (pintype "passive"))
      (node (ref "Q1") (pin "9") (pinfunction "D_9") (pintype "passive"))
      (node (ref "X1") (pin "11") (pinfunction "1_11") (pintype "passive"))
    )
    (net (code "33") (name "PA0_SMBUS_SDA") (class "Default")
      (node (ref "IC2") (pin "1") (pinfunction "PA0/I2C0_SDA#0/TIM0_CC0#0,1_1") (pintype "bidirectional"))
      (node (ref "R2") (pin "2") (pinfunction "2_2") (pintype "passive"))
      (node (ref "X1") (pin "2") (pinfunction "1_2") (pintype "passive"))
    )
    (net (code "34") (name "PA1_SMBUS_SCL") (class "Default")
      (node (ref "IC2") (pin "2") (pinfunction "PA1/CMU_CLK1#0/I2C0_SCL#0/TIM0_CC1#0,1_2") (pintype "bidirectional"))
      (node (ref "R1") (pin "2") (pinfunction "2_2") (pintype "passive"))
      (node (ref "X1") (pin "1") (pinfunction "1_1") (pintype "passive"))
    )
    (net (code "35") (name "PA2_POWER_LED") (class "Default")
      (node (ref "IC2") (pin "3") (pinfunction "PA2/CMU_CLK0#0/TIM0_CC2#0,1_3") (pintype "bidirectional"))
      (node (ref "R4") (pin "1") (pinfunction "1_1") (pintype "passive"))
    )
    (net (code "36") (name "PA3_KEY_S1") (class "Default")
      (node (ref "C26") (pin "2") (pinfunction "2_2") (pintype "passive"))
      (node (ref "IC2") (pin "4") (pinfunction "PA3/TIM0_CDTI0#0_4") (pintype "bidirectional"))
      (node (ref "R17") (pin "1") (pinfunction "1_1") (pintype "passive"))
      (node (ref "S1") (pin "1") (pinfunction "1_1") (pintype "passive"))
      (node (ref "S1") (pin "2") (pinfunction "2_2") (pintype "passive"))
    )
    (net (code "37") (name "PA4_KEY_S2") (class "Default")
      (node (ref "C27") (pin "2") (pinfunction "2_2") (pintype "passive"))
      (node (ref "IC2") (pin "5") (pinfunction "PA4/TIM0_CDTI1#0_5") (pintype "bidirectional"))
      (node (ref "R19") (pin "1") (pinfunction "1_1") (pintype "passive"))
      (node (ref "S2") (pin "1") (pinfunction "1_1") (pintype "passive"))
      (node (ref "S2") (pin "2") (pinfunction "2_2") (pintype "passive"))
    )
    (net (code "38") (name "PA5_LOG_FLUSH_LED") (class "Default")
      (node (ref "IC2") (pin "6") (pinfunction "PA5/LEU1_TX#1/TIM0_CDTI2#0_6") (pintype "bidirectional"))
      (node (ref "R5") (pin "1") (pinfunction "1_1") (pintype "passive"))
    )
    (net (code "39") (name "PA6_RFID_POWER") (class "Default")
      (node (ref "IC2") (pin "7") (pinfunction "PA6/LEU1_RX#1_7") (pintype "bidirectional"))
      (node (ref "R35") (pin "1") (pinfunction "1_1") (pintype "passive"))
    )
    (net (code "40") (name "PB7_LFXTAL_P") (class "Default")
      (node (ref "C18") (pin "2") (pinfunction "2_2") (pintype "passive"))
      (node (ref "IC2") (pin "15") (pinfunction "PB7/LFXTAL_P/US1_CLK#0_15") (pintype "bidirectional"))
      (node (ref "Q3") (pin "2") (pinfunction "2_2") (pintype "passive"))
    )
    (net (code "41") (name "PB8_LFXTAL_N") (class "Default")
      (node (ref "C13") (pin "2") (pinfunction "2_2") (pintype "passive"))
      (node (ref "IC2") (pin "16") (pinfunction "PB8/LFXTAL_N/US1_CS#0_16") (pintype "bidirectional"))
      (node (ref "Q3") (pin "1") (pinfunction "1_1") (pintype "passive"))
    )
    (net (code "42") (name "PB11_POWER_GOOD") (class "Default")
      (node (ref "IC1") (pin "8") (pinfunction "PG_8") (pintype "output"))
      (node (ref "IC2") (pin "21") (pinfunction "PB11/DAC0_OUT0/OPAMP_OUT0/LETIM0_OUT0#1_21") (pintype "bidirectional"))
      (node (ref "R9") (pin "2") (pinfunction "2_2") (pintype "passive"))
    )
    (net (code "43") (name "PB13_HFXTAL_P") (class "Default")
      (node (ref "C17") (pin "2") (pinfunction "2_2") (pintype "passive"))
      (node (ref "IC2") (pin "24") (pinfunction "PB13/HFXTAL_P/LEU0_TX#1_24") (pintype "bidirectional"))
      (node (ref "Q2") (pin "2") (pinfunction "2_2") (pintype "passive"))
    )
    (net (code "44") (name "PB14_HFXTAL_N") (class "Default")
      (node (ref "C12") (pin "2") (pinfunction "2_2") (pintype "passive"))
      (node (ref "IC2") (pin "25") (pinfunction "PB14/HFXTAL_N/LEU0_RX#1_25") (pintype "bidirectional"))
      (node (ref "Q2") (pin "1") (pinfunction "1_1") (pintype "passive"))
    )
    (net (code "45") (name "PC0_RFID_RX") (class "Default")
      (node (ref "IC2") (pin "9") (pinfunction "PC0/ACMP0_CH0/PCNT0_S0IN#2/US1_TX#0_9") (pintype "bidirectional"))
      (node (ref "X1") (pin "5") (pinfunction "1_5") (pintype "passive"))
    )
    (net (code "46") (name "PC1_RFID_TX") (class "Default")
      (node (ref "IC2") (pin "10") (pinfunction "PC1/ACMP0_CH1/PCNT0_S1IN#2/US1_RX#0_10") (pintype "bidirectional"))
      (node (ref "X1") (pin "4") (pinfunction "1_4") (pintype "passive"))
    )
    (net (code "47") (name "PC2_SD_SDO") (class "Default")
      (node (ref "IC2") (pin "11") (pinfunction "PC2/ACMP0_CH2/US2_TX_11") (pintype "bidirectional"))
      (node (ref "SD1") (pin "2") (pinfunction "2_2") (pintype "bidirectional"))
    )
    (net (code "48") (name "PC3_SD_SDI") (class "Default")
      (node (ref "IC2") (pin "12") (pinfunction "PC3/ACMP0_CH3/US2_RX_12") (pintype "bidirectional"))
      (node (ref "R29") (pin "1") (pinfunction "1_1") (pintype "passive"))
      (node (ref "SD1") (pin "7") (pinfunction "7_7") (pintype "bidirectional"))
    )
    (net (code "49") (name "PC4_SD_CLK") (class "Default")
      (node (ref "IC2") (pin "13") (pinfunction "PC4/ACMP0_CH4/LETIM0_OUT0#3/PCNT1_S0IN/US2_CLK_13") (pintype "bidirectional"))
      (node (ref "SD1") (pin "5") (pinfunction "5_5") (pintype "bidirectional"))
    )
    (net (code "50") (name "PC5_SD_CS") (class "Default")
      (node (ref "IC2") (pin "14") (pinfunction "PC5/ACMP0_CH5/LETIM0_OUT1#3/PCNT1_S1IN/US2_CS_14") (pintype "bidirectional"))
      (node (ref "SD1") (pin "1") (pinfunction "1_1") (pintype "bidirectional"))
    )
    (net (code "51") (name "PC6_SD_CD") (class "Default")
      (node (ref "IC2") (pin "37") (pinfunction "PC6/ACMP0_CH6/I2C0_SDA#2/LEU1_TX#0_37") (pintype "bidirectional"))
      (node (ref "R30") (pin "1") (pinfunction "1_1") (pintype "passive"))
      (node (ref "SD1") (pin "CDS") (pinfunction "CDS_CDS") (pintype "passive"))
    )
    (net (code "52") (name "PC7_SD_WP") (class "Default")
      (node (ref "IC2") (pin "38") (pinfunction "PC7/ACMP0_CH7/I2C0_SCL#2/LEU1_RX#0_38") (pintype "bidirectional"))
      (node (ref "SD1") (pin "WPS") (pinfunction "WPS_WPS") (pintype "passive"))
    )
    (net (code "53") (name "PC12_SD_PULLUP") (class "Default")
      (node (ref "IC2") (pin "45") (pinfunction "PC12/ACMP1_CH4/CMU_CLK0#1_45") (pintype "bidirectional"))
      (node (ref "R30") (pin "2") (pinfunction "2_2") (pintype "passive"))
    )
    (net (code "54") (name "PD0_SD_POWER") (class "Default")
      (node (ref "IC2") (pin "28") (pinfunction "PD0/ADC0_CH0/PCNT2_S0IN#0/US1_TX#1_28") (pintype "bidirectional"))
      (node (ref "R14") (pin "2") (pinfunction "2_2") (pintype "passive"))
    )
    (net (code "55") (name "PD1_DCF77_ENABLE") (class "Default")
      (node (ref "IC2") (pin "29") (pinfunction "PD1/ADC0_CH1/PCNT2_S1IN#0/TIM0_CC0#3/US1_RX#1_29") (pintype "bidirectional"))
      (node (ref "X2") (pin "3") (pinfunction "1_3") (pintype "passive"))
    )
    (net (code "56") (name "PD2_DCF77_SIGNAL") (class "Default")
      (node (ref "IC2") (pin "30") (pinfunction "PD2/ADC0_CH2/TIM0_CC1#3/US1_CLK#1_30") (pintype "bidirectional"))
      (node (ref "X2") (pin "4") (pinfunction "1_4") (pintype "passive"))
    )
    (net (code "57") (name "PD4_LEUART_TX") (class "Default")
      (node (ref "IC2") (pin "32") (pinfunction "PD4/ADC0_CH4/LEU0_TX#0_32") (pintype "bidirectional"))
      (node (ref "R27") (pin "1") (pinfunction "1_1") (pintype "passive"))
    )
    (net (code "58") (name "PD5_LEUART_RX") (class "Default")
      (node (ref "IC2") (pin "33") (pinfunction "PD5/ADC0_CH5/LEU0_RX#0_33") (pintype "bidirectional"))
      (node (ref "R26") (pin "1") (pinfunction "1_1") (pintype "passive"))
    )
    (net (code "59") (name "PD6_LB_OUTER") (class "Default")
      (node (ref "IC2") (pin "34") (pinfunction "PD6/ADC0_CH6/I2C0_SDA#1/LETIM0_OUT0#0_34") (pintype "bidirectional"))
      (node (ref "X1") (pin "8") (pinfunction "1_8") (pintype "passive"))
    )
    (net (code "60") (name "PD7_LB_INNER") (class "Default")
      (node (ref "IC2") (pin "35") (pinfunction "PD7/ADC0_CH7/I2C0_SCL#1/LETIM0_OUT1#0_35") (pintype "bidirectional"))
      (node (ref "X1") (pin "7") (pinfunction "1_7") (pintype "passive"))
    )
    (net (code "61") (name "PD8_LCD_POWER") (class "Default")
      (node (ref "IC2") (pin "36") (pinfunction "PD8/CMU_CLK1#1_36") (pintype "bidirectional"))
      (node (ref "R31") (pin "2") (pinfunction "2_2") (pintype "passive"))
    )
    (net (code "62") (name "PE8_LCD_D0") (class "Default")
      (node (ref "IC2") (pin "56") (pinfunction "PE8/PCNT2_S0IN#1_56") (pintype "bidirectional"))
      (node (ref "LCD1") (pin "35") (pinfunction "D0_35") (pintype "bidirectional"))
    )
    (net (code "63") (name "PE9_LCD_D1") (class "Default")
      (node (ref "IC2") (pin "57") (pinfunction "PE9/PCNT2_S1IN#1_57") (pintype "bidirectional"))
      (node (ref "LCD1") (pin "34") (pinfunction "D1_34") (pintype "bidirectional"))
    )
    (net (code "64") (name "PE10_LCD_D2") (class "Default")
      (node (ref "IC2") (pin "58") (pinfunction "PE10/TIM1_CC0#1/US0_TX#0_58") (pintype "bidirectional"))
      (node (ref "LCD1") (pin "33") (pinfunction "D2_33") (pintype "bidirectional"))
    )
    (net (code "65") (name "PE11_LCD_D3") (class "Default")
      (node (ref "IC2") (pin "59") (pinfunction "PE11/TIM1_CC1#1/US0_RX#0_59") (pintype "bidirectional"))
      (node (ref "LCD1") (pin "32") (pinfunction "D3_32") (pintype "bidirectional"))
    )
    (net (code "66") (name "PE12_LCD_D4") (class "Default")
      (node (ref "IC2") (pin "60") (pinfunction "PE12/TIM1_CC2#1/US0_CLK#0_60") (pintype "bidirectional"))
      (node (ref "LCD1") (pin "31") (pinfunction "D4_31") (pintype "bidirectional"))
    )
    (net (code "67") (name "PE13_LCD_D5") (class "Default")
      (node (ref "IC2") (pin "61") (pinfunction "PE13/ACMP0_O/US0_CS#0_61") (pintype "bidirectional"))
      (node (ref "LCD1") (pin "30") (pinfunction "D5_30") (pintype "bidirectional"))
    )
    (net (code "68") (name "PE14_LCD_D6") (class "Default")
      (node (ref "IC2") (pin "62") (pinfunction "PE14/LEU0_TX#2_62") (pintype "bidirectional"))
      (node (ref "LCD1") (pin "29") (pinfunction "D6_29") (pintype "bidirectional"))
    )
    (net (code "69") (name "PE15_LCD_D7") (class "Default")
      (node (ref "IC2") (pin "63") (pinfunction "PE15/LEU0_RX#2_63") (pintype "bidirectional"))
      (node (ref "LCD1") (pin "28") (pinfunction "D7_28") (pintype "bidirectional"))
    )
    (net (code "70") (name "PF0_DBG_SWCLK") (class "Default")
      (node (ref "IC2") (pin "49") (pinfunction "PF0/DBG_SWCLK#0,1/LETIM0_OUT0#2_49") (pintype "bidirectional"))
      (node (ref "SV1") (pin "4") (pinfunction "4_4") (pintype "passive"))
    )
    (net (code "71") (name "PF1_DBG_SWDIO") (class "Default")
      (node (ref "IC2") (pin "50") (pinfunction "PF1/DBG_SWDIO#0,1/LETIM0_OUT1#2_50") (pintype "bidirectional"))
      (node (ref "SV1") (pin "2") (pinfunction "2_2") (pintype "passive"))
    )
    (net (code "72") (name "PF2_DBG_SWO") (class "Default")
      (node (ref "IC2") (pin "51") (pinfunction "PF2/ACMP1_O/DBG_SWO#0_51") (pintype "bidirectional"))
      (node (ref "SV1") (pin "6") (pinfunction "6_6") (pintype "passive"))
    )
    (net (code "73") (name "PF3_LCD_ENABLE") (class "Default")
      (node (ref "IC2") (pin "52") (pinfunction "PF3/TIM0_CDTI0#2_52") (pintype "bidirectional"))
      (node (ref "LCD1") (pin "36") (pinfunction "E_36") (pintype "input"))
    )
    (net (code "74") (name "PF4_LCD_RW") (class "Default")
      (node (ref "IC2") (pin "53") (pinfunction "PF4/TIM0_CDTI1#2_53") (pintype "bidirectional"))
      (node (ref "LCD1") (pin "37") (pinfunction "R/~{W}_37") (pintype "input"))
    )
    (net (code "75") (name "PF5_LCD_RS") (class "Default")
      (node (ref "IC2") (pin "54") (pinfunction "PF5/TIM0_CDTI2#2_54") (pintype "bidirectional"))
      (node (ref "LCD1") (pin "39") (pinfunction "RS_39") (pintype "input"))
    )
    (net (code "76") (name "RFID_GND") (class "Default")
      (node (ref "T5") (pin "1") (pinfunction "D_1") (pintype "passive"))
      (node (ref "X1") (pin "6") (pinfunction "1_6") (pintype "passive"))
    )
    (net (code "77") (name "RXD_HOST") (class "Default")
      (node (ref "J1") (pin "P$3") (pinfunction "3-RIGHT_P$3") (pintype "bidirectional"))
      (node (ref "R27") (pin "2") (pinfunction "2_2") (pintype "passive"))
    )
    (net (code "78") (name "SD_+3.3V") (class "Default")
      (node (ref "C29") (pin "1") (pinfunction "1_1") (pintype "passive"))
      (node (ref "C30") (pin "1") (pinfunction "1_1") (pintype "passive"))
      (node (ref "R21") (pin "2") (pinfunction "2_2") (pintype "passive"))
      (node (ref "R25") (pin "2") (pinfunction "2_2") (pintype "passive"))
      (node (ref "R28") (pin "2") (pinfunction "2_2") (pintype "passive"))
      (node (ref "R29") (pin "2") (pinfunction "2_2") (pintype "passive"))
      (node (ref "SD1") (pin "4") (pinfunction "4_4") (pintype "bidirectional"))
      (node (ref "T2") (pin "1") (pinfunction "D_1") (pintype "passive"))
    )
    (net (code "79") (name "TXD_HOST") (class "Default")
      (node (ref "J1") (pin "P$2") (pinfunction "2-LEFT_P$2") (pintype "bidirectional"))
      (node (ref "R26") (pin "2") (pinfunction "2_2") (pintype "passive"))
    )
    (net (code "80") (name "VFRONT") (class "Default")
      (node (ref "C5") (pin "+") (pinfunction "+_+") (pintype "passive"))
      (node (ref "C7") (pin "1") (pinfunction "1_1") (pintype "passive"))
      (node (ref "D1") (pin "1") (pinfunction "C_1") (pintype "passive"))
      (node (ref "X1") (pin "10") (pinfunction "1_10") (pintype "passive"))
    )
    (net (code "81") (name "VMCU") (class "Default")
      (node (ref "C14") (pin "2") (pinfunction "2_2") (pintype "passive"))
      (node (ref "C15") (pin "2") (pinfunction "2_2") (pintype "passive"))
      (node (ref "C16") (pin "2") (pinfunction "2_2") (pintype "passive"))
      (node (ref "C20") (pin "2") (pinfunction "2_2") (pintype "passive"))
      (node (ref "C22") (pin "2") (pinfunction "2_2") (pintype "passive"))
      (node (ref "C24") (pin "2") (pinfunction "2_2") (pintype "passive"))
      (node (ref "C25") (pin "2") (pinfunction "2_2") (pintype "passive"))
      (node (ref "C9") (pin "2") (pinfunction "2_2") (pintype "passive"))
      (node (ref "D3") (pin "1") (pinfunction "C_1") (pintype "passive"))
      (node (ref "IC2") (pin "26") (pinfunction "IOVDD_3_26") (pintype "power_in"))
      (node (ref "IC2") (pin "39") (pinfunction "VDD_DREG_39") (pintype "power_in"))
      (node (ref "IC2") (pin "55") (pinfunction "IOVDD_5_55") (pintype "power_in"))
      (node (ref "IC2") (pin "8") (pinfunction "IOVDD_0_8") (pintype "power_in"))
      (node (ref "L2") (pin "1") (pinfunction "1_1") (pintype "passive"))
      (node (ref "R1") (pin "1") (pinfunction "1_1") (pintype "passive"))
      (node (ref "R12") (pin "1") (pinfunction "1_1") (pintype "passive"))
      (node (ref "R17") (pin "2") (pinfunction "2_2") (pintype "passive"))
      (node (ref "R19") (pin "2") (pinfunction "2_2") (pintype "passive"))
      (node (ref "R2") (pin "1") (pinfunction "1_1") (pintype "passive"))
      (node (ref "R20") (pin "2") (pinfunction "2_2") (pintype "passive"))
      (node (ref "R32") (pin "2") (pinfunction "2_2") (pintype "passive"))
      (node (ref "SV1") (pin "1") (pinfunction "1_1") (pintype "passive"))
      (node (ref "T4") (pin "2") (pinfunction "S_2") (pintype "passive"))
      (node (ref "X2") (pin "1") (pinfunction "1_1") (pintype "passive"))
    )
    (net (code "82") (name "VSD") (class "Default")
      (node (ref "C6") (pin "+") (pinfunction "+_+") (pintype "passive"))
      (node (ref "C8") (pin "1") (pinfunction "1_1") (pintype "passive"))
      (node (ref "D2") (pin "1") (pinfunction "C_1") (pintype "passive"))
      (node (ref "R15") (pin "2") (pinfunction "2_2") (pintype "passive"))
      (node (ref "T2") (pin "2") (pinfunction "S_2") (pintype "passive"))
    )
    (net (code "83") (name "unconnected-(IC2A-PA8{slash}TIM2_CC0#0-Pad17)") (class "Default")
      (node (ref "IC2") (pin "17") (pinfunction "PA8/TIM2_CC0#0_17") (pintype "bidirectional"))
    )
    (net (code "84") (name "unconnected-(IC2A-PA9{slash}TIM2_CC1#0-Pad18)") (class "Default")
      (node (ref "IC2") (pin "18") (pinfunction "PA9/TIM2_CC1#0_18") (pintype "bidirectional"))
    )
    (net (code "85") (name "unconnected-(IC2A-PA10{slash}TIM2_CC2#0-Pad19)") (class "Default")
      (node (ref "IC2") (pin "19") (pinfunction "PA10/TIM2_CC2#0_19") (pintype "bidirectional"))
    )
    (net (code "86") (name "unconnected-(IC2B-PB12{slash}DAC0_OUT1{slash}OPAMP_OUT1{slash}LETIM0_OUT1#1-Pad22)") (class "Default")
      (node (ref "IC2") (pin "22") (pinfunction "PB12/DAC0_OUT1/OPAMP_OUT1/LETIM0_OUT1#1_22") (pintype "bidirectional"))
    )
    (net (code "87") (name "unconnected-(IC2C-PC8{slash}ACMP1_CH0{slash}TIM2_CC0#2{slash}US0_CS#2-Pad41)") (class "Default")
      (node (ref "IC2") (pin "41") (pinfunction "PC8/ACMP1_CH0/TIM2_CC0#2/US0_CS#2_41") (pintype "bidirectional"))
    )
    (net (code "88") (name "unconnected-(IC2C-PC9{slash}ACMP1_CH1{slash}TIM2_CC1#2{slash}US0_CLK#2-Pad42)") (class "Default")
      (node (ref "IC2") (pin "42") (pinfunction "PC9/ACMP1_CH1/TIM2_CC1#2/US0_CLK#2_42") (pintype "bidirectional"))
    )
    (net (code "89") (name "unconnected-(IC2C-PC10{slash}ACMP1_CH2{slash}TIM2_CC2#2{slash}US0_RX#2-Pad43)") (class "Default")
      (node (ref "IC2") (pin "43") (pinfunction "PC10/ACMP1_CH2/TIM2_CC2#2/US0_RX#2_43") (pintype "bidirectional"))
    )
    (net (code "90") (name "unconnected-(IC2C-PC11{slash}ACMP1_CH3{slash}US0_TX#2-Pad44)") (class "Default")
      (node (ref "IC2") (pin "44") (pinfunction "PC11/ACMP1_CH3/US0_TX#2_44") (pintype "bidirectional"))
    )
    (net (code "91") (name "unconnected-(IC2C-PC13{slash}ACMP1_CH5{slash}PCNT0_S0IN#0{slash}TIM0_CDTI0#1,3{slash}TIM1_CC0#0-Pad46)") (class "Default")
      (node (ref "IC2") (pin "46") (pinfunction "PC13/ACMP1_CH5/PCNT0_S0IN#0/TIM0_CDTI0#1,3/TIM1_CC0#0_46") (pintype "bidirectional"))
    )
    (net (code "92") (name "unconnected-(IC2C-PC14{slash}ACMP1_CH6{slash}PCNT0_S1IN#0{slash}TIM0_CDTI1#1,3{slash}TIM1_CC1#0-Pad47)") (class "Default")
      (node (ref "IC2") (pin "47") (pinfunction "PC14/ACMP1_CH6/PCNT0_S1IN#0/TIM0_CDTI1#1,3/TIM1_CC1#0_47") (pintype "bidirectional"))
    )
    (net (code "93") (name "unconnected-(IC2C-PC15{slash}ACMP1_CH7{slash}DBG_SWO#1{slash}TIM0_CDTI2#1,3{slash}TIM1_CC2#0-Pad48)") (class "Default")
      (node (ref "IC2") (pin "48") (pinfunction "PC15/ACMP1_CH7/DBG_SWO#1/TIM0_CDTI2#1,3/TIM1_CC2#0_48") (pintype "bidirectional"))
    )
    (net (code "94") (name "unconnected-(IC2D-PD3{slash}ADC0_CH3{slash}TIM0_CC2#3{slash}US1_CS#1-Pad31)") (class "Default")
      (node (ref "IC2") (pin "31") (pinfunction "PD3/ADC0_CH3/TIM0_CC2#3/US1_CS#1_31") (pintype "bidirectional"))
    )
    (net (code "95") (name "unconnected-(SD1-PadG1)") (class "Default")
      (node (ref "SD1") (pin "G1") (pinfunction "G1_G1") (pintype "passive"))
    )
    (net (code "96") (name "unconnected-(SD1-PadG2)") (class "Default")
      (node (ref "SD1") (pin "G2") (pinfunction "G2_G2") (pintype "passive"))
    )
    (net (code "97") (name "unconnected-(SD1-PadG3)") (class "Default")
      (node (ref "SD1") (pin "G3") (pinfunction "G3_G3") (pintype "passive"))
    )
    (net (code "98") (name "unconnected-(SD1-PadG4)") (class "Default")
      (node (ref "SD1") (pin "G4") (pinfunction "G4_G4") (pintype "passive"))
    )
    (net (code "99") (name "unconnected-(SV1-Pad7)") (class "Default")
      (node (ref "SV1") (pin "7") (pinfunction "7_7") (pintype "passive"))
    )
    (net (code "100") (name "unconnected-(SV1-Pad8)") (class "Default")
      (node (ref "SV1") (pin "8") (pinfunction "8_8") (pintype "passive"))
    )
  )
)
